# LED.net
KiCad netlist of a schematic drawn in Altium Designer
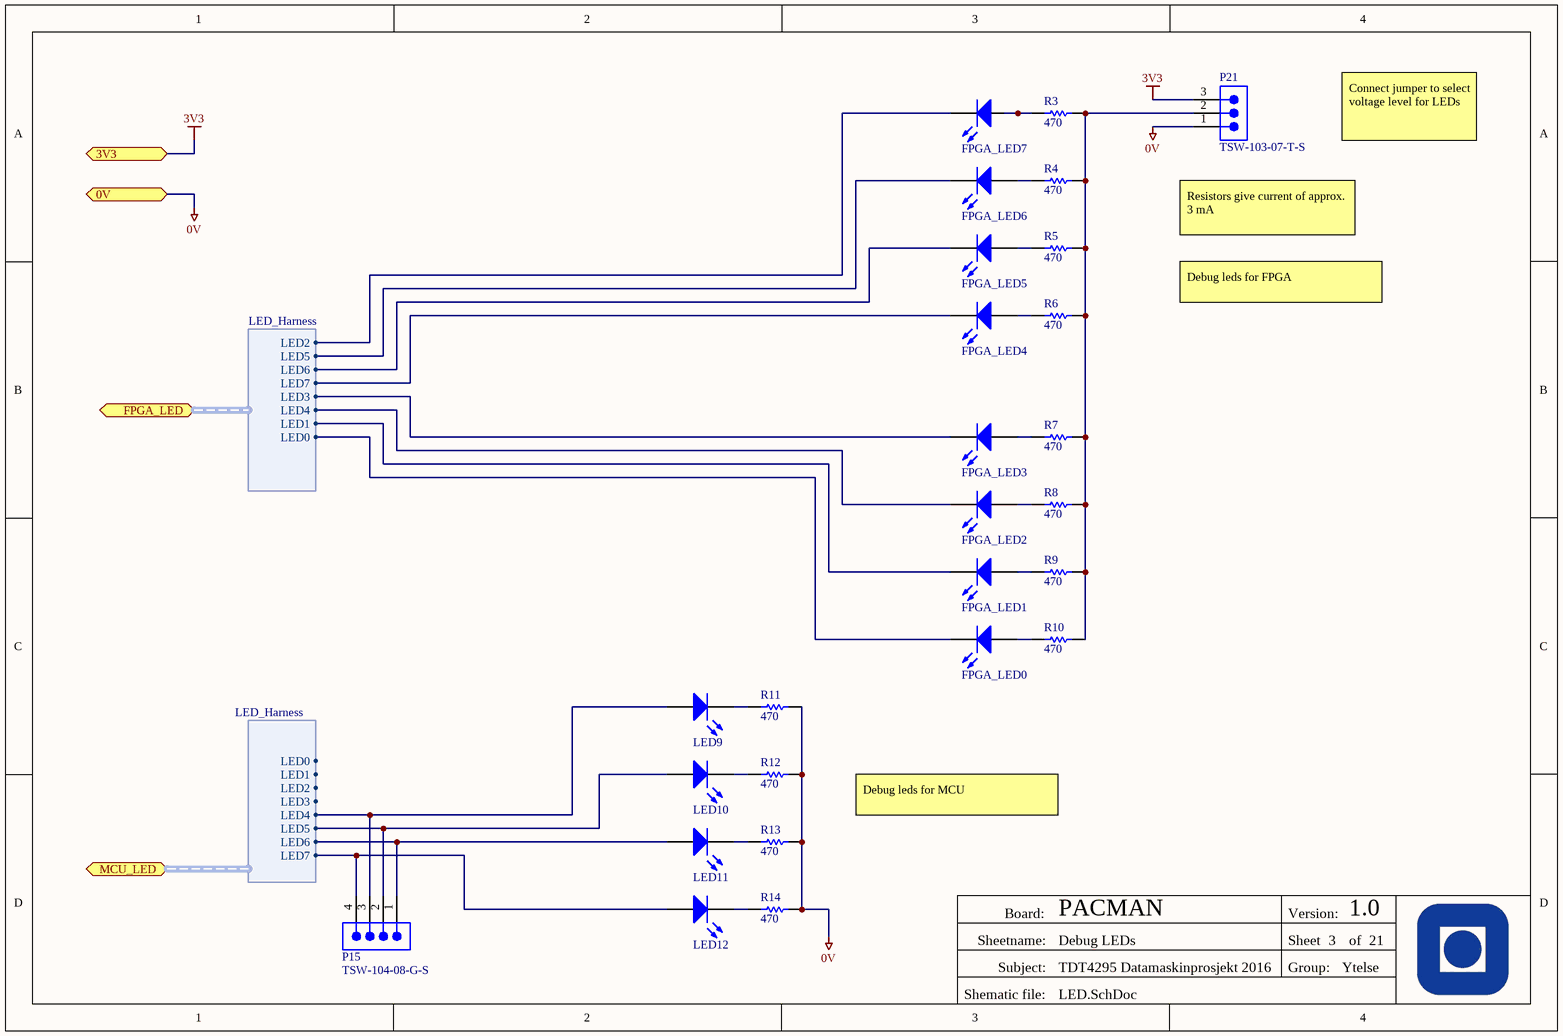
[diagram p0: LED.SchDoc]

(export (version "E")
  (design (tool "Eeschema 10.0.6"))
  (components
    (comp (ref "FPGA_LED0")
      (value "150060RS75000")
      (footprint "0603_A")
      (description "SMD mono-color Chip LED, WL-SMCW, Red")
      (fields (field (name "MANUFACTURER") "Wuerth Elektronik"))
      (libsource (lib "Altium Content Vault") (part "CMP-1426-00001-1"))
    )
    (comp (ref "FPGA_LED1")
      (value "150060RS75000")
      (footprint "0603_A")
      (description "SMD mono-color Chip LED, WL-SMCW, Red")
      (fields (field (name "MANUFACTURER") "Wuerth Elektronik"))
      (libsource (lib "Altium Content Vault") (part "CMP-1426-00001-1"))
    )
    (comp (ref "FPGA_LED2")
      (value "150060RS75000")
      (footprint "0603_A")
      (description "SMD mono-color Chip LED, WL-SMCW, Red")
      (fields (field (name "MANUFACTURER") "Wuerth Elektronik"))
      (libsource (lib "Altium Content Vault") (part "CMP-1426-00001-1"))
    )
    (comp (ref "FPGA_LED3")
      (value "150060RS75000")
      (footprint "0603_A")
      (description "SMD mono-color Chip LED, WL-SMCW, Red")
      (fields (field (name "MANUFACTURER") "Wuerth Elektronik"))
      (libsource (lib "Altium Content Vault") (part "CMP-1426-00001-1"))
    )
    (comp (ref "FPGA_LED4")
      (value "150060RS75000")
      (footprint "0603_A")
      (description "SMD mono-color Chip LED, WL-SMCW, Red")
      (fields (field (name "MANUFACTURER") "Wuerth Elektronik"))
      (libsource (lib "Altium Content Vault") (part "CMP-1426-00001-1"))
    )
    (comp (ref "FPGA_LED5")
      (value "150060RS75000")
      (footprint "0603_A")
      (description "SMD mono-color Chip LED, WL-SMCW, Red")
      (fields (field (name "MANUFACTURER") "Wuerth Elektronik"))
      (libsource (lib "Altium Content Vault") (part "CMP-1426-00001-1"))
    )
    (comp (ref "FPGA_LED6")
      (value "150060RS75000")
      (footprint "0603_A")
      (description "SMD mono-color Chip LED, WL-SMCW, Red")
      (fields (field (name "MANUFACTURER") "Wuerth Elektronik"))
      (libsource (lib "Altium Content Vault") (part "CMP-1426-00001-1"))
    )
    (comp (ref "FPGA_LED7")
      (value "150060RS75000")
      (footprint "0603_A")
      (description "SMD mono-color Chip LED, WL-SMCW, Red")
      (fields (field (name "MANUFACTURER") "Wuerth Elektronik"))
      (libsource (lib "Altium Content Vault") (part "CMP-1426-00001-1"))
    )
    (comp (ref "LED9")
      (value "150060RS75000")
      (footprint "0603_A")
      (description "SMD mono-color Chip LED, WL-SMCW, Red")
      (fields (field (name "MANUFACTURER") "Wuerth Elektronik"))
      (libsource (lib "Altium Content Vault") (part "CMP-1426-00001-1"))
    )
    (comp (ref "LED10")
      (value "150060RS75000")
      (footprint "0603_A")
      (description "SMD mono-color Chip LED, WL-SMCW, Red")
      (fields (field (name "MANUFACTURER") "Wuerth Elektronik"))
      (libsource (lib "Altium Content Vault") (part "CMP-1426-00001-1"))
    )
    (comp (ref "LED11")
      (value "150060RS75000")
      (footprint "0603_A")
      (description "SMD mono-color Chip LED, WL-SMCW, Red")
      (fields (field (name "MANUFACTURER") "Wuerth Elektronik"))
      (libsource (lib "Altium Content Vault") (part "CMP-1426-00001-1"))
    )
    (comp (ref "LED12")
      (value "150060RS75000")
      (footprint "0603_A")
      (description "SMD mono-color Chip LED, WL-SMCW, Red")
      (fields (field (name "MANUFACTURER") "Wuerth Elektronik"))
      (libsource (lib "Altium Content Vault") (part "CMP-1426-00001-1"))
    )
    (comp (ref "P15")
      (value "TSW-104-08-G-S")
      (footprint "SMTC-TSW-104-08-X-S")
      (description "0.025\" SQ Post Header, Through-hole, Vertical, -55 to 125 degC, 2.54 mm Pitch, 4-Pin, Male, RoHS")
      (fields (field (name "MANUFACTURER") "Samtec"))
      (libsource (lib "Altium Content Vault") (part "SMTC-TSW-104-08-X-S"))
    )
    (comp (ref "P21")
      (value "TSW-103-07-T-S")
      (footprint "SMTC-TSW-103-07-X-S")
      (fields (field (name "MANUFACTURER") "Samtec"))
      (libsource (lib "Altium Content Vault") (part "SMTC-TSW-103-X-X-S-X"))
    )
    (comp (ref "R3")
      (value "470")
      (footprint "RESC0603(1608)_N")
      (description "470R 0.1W 5% 0603 (1608 Metric)  SMD")
      (fields (field (name "TOLERANCE") "5 %") (field (name "POWER") "0.1 W"))
      (libsource (lib "Altium Content Vault") (part "CMP-1012-00066-1"))
    )
    (comp (ref "R4")
      (value "470")
      (footprint "RESC0603(1608)_N")
      (description "470R 0.1W 5% 0603 (1608 Metric)  SMD")
      (fields (field (name "TOLERANCE") "5 %") (field (name "POWER") "0.1 W"))
      (libsource (lib "Altium Content Vault") (part "CMP-1012-00066-1"))
    )
    (comp (ref "R5")
      (value "470")
      (footprint "RESC0603(1608)_N")
      (description "470R 0.1W 5% 0603 (1608 Metric)  SMD")
      (fields (field (name "TOLERANCE") "5 %") (field (name "POWER") "0.1 W"))
      (libsource (lib "Altium Content Vault") (part "CMP-1012-00066-1"))
    )
    (comp (ref "R6")
      (value "470")
      (footprint "RESC0603(1608)_N")
      (description "470R 0.1W 5% 0603 (1608 Metric)  SMD")
      (fields (field (name "TOLERANCE") "5 %") (field (name "POWER") "0.1 W"))
      (libsource (lib "Altium Content Vault") (part "CMP-1012-00066-1"))
    )
    (comp (ref "R7")
      (value "470")
      (footprint "RESC0603(1608)_N")
      (description "470R 0.1W 5% 0603 (1608 Metric)  SMD")
      (fields (field (name "TOLERANCE") "5 %") (field (name "POWER") "0.1 W"))
      (libsource (lib "Altium Content Vault") (part "CMP-1012-00066-1"))
    )
    (comp (ref "R8")
      (value "470")
      (footprint "RESC0603(1608)_N")
      (description "470R 0.1W 5% 0603 (1608 Metric)  SMD")
      (fields (field (name "TOLERANCE") "5 %") (field (name "POWER") "0.1 W"))
      (libsource (lib "Altium Content Vault") (part "CMP-1012-00066-1"))
    )
    (comp (ref "R9")
      (value "470")
      (footprint "RESC0603(1608)_N")
      (description "470R 0.1W 5% 0603 (1608 Metric)  SMD")
      (fields (field (name "TOLERANCE") "5 %") (field (name "POWER") "0.1 W"))
      (libsource (lib "Altium Content Vault") (part "CMP-1012-00066-1"))
    )
    (comp (ref "R10")
      (value "470")
      (footprint "RESC0603(1608)_N")
      (description "470R 0.1W 5% 0603 (1608 Metric)  SMD")
      (fields (field (name "TOLERANCE") "5 %") (field (name "POWER") "0.1 W"))
      (libsource (lib "Altium Content Vault") (part "CMP-1012-00066-1"))
    )
    (comp (ref "R11")
      (value "470")
      (footprint "RESC0603(1608)_N")
      (description "470R 0.1W 5% 0603 (1608 Metric)  SMD")
      (fields (field (name "TOLERANCE") "5 %") (field (name "POWER") "0.1 W"))
      (libsource (lib "Altium Content Vault") (part "CMP-1012-00066-1"))
    )
    (comp (ref "R12")
      (value "470")
      (footprint "RESC0603(1608)_N")
      (description "470R 0.1W 5% 0603 (1608 Metric)  SMD")
      (fields (field (name "TOLERANCE") "5 %") (field (name "POWER") "0.1 W"))
      (libsource (lib "Altium Content Vault") (part "CMP-1012-00066-1"))
    )
    (comp (ref "R13")
      (value "470")
      (footprint "RESC0603(1608)_N")
      (description "470R 0.1W 5% 0603 (1608 Metric)  SMD")
      (fields (field (name "TOLERANCE") "5 %") (field (name "POWER") "0.1 W"))
      (libsource (lib "Altium Content Vault") (part "CMP-1012-00066-1"))
    )
    (comp (ref "R14")
      (value "470")
      (footprint "RESC0603(1608)_N")
      (description "470R 0.1W 5% 0603 (1608 Metric)  SMD")
      (fields (field (name "TOLERANCE") "5 %") (field (name "POWER") "0.1 W"))
      (libsource (lib "Altium Content Vault") (part "CMP-1012-00066-1"))
    )
  )
  (nets
    (net (code "3") (name "0V") (class "Default")
      (node (ref "P21") (pin "1") (pinfunction "1_1") (pintype "passive"))
      (node (ref "R11") (pin "2") (pinfunction "2_2") (pintype "passive"))
      (node (ref "R12") (pin "2") (pinfunction "2_2") (pintype "passive"))
      (node (ref "R13") (pin "2") (pinfunction "2_2") (pintype "passive"))
      (node (ref "R14") (pin "2") (pinfunction "2_2") (pintype "passive"))
    )
    (net (code "4") (name "3V3") (class "Default")
      (node (ref "P21") (pin "3") (pinfunction "3_3") (pintype "passive"))
    )
    (net (code "5") (name "Net-(FPGA_LED0-A)") (class "Default")
      (node (ref "FPGA_LED0") (pin "2") (pinfunction "A_2") (pintype "passive"))
      (node (ref "R10") (pin "1") (pinfunction "1_1") (pintype "passive"))
    )
    (net (code "6") (name "Net-(FPGA_LED1-A)") (class "Default")
      (node (ref "FPGA_LED1") (pin "2") (pinfunction "A_2") (pintype "passive"))
      (node (ref "R9") (pin "1") (pinfunction "1_1") (pintype "passive"))
    )
    (net (code "7") (name "Net-(FPGA_LED2-A)") (class "Default")
      (node (ref "FPGA_LED2") (pin "2") (pinfunction "A_2") (pintype "passive"))
      (node (ref "R8") (pin "1") (pinfunction "1_1") (pintype "passive"))
    )
    (net (code "8") (name "Net-(FPGA_LED3-A)") (class "Default")
      (node (ref "FPGA_LED3") (pin "2") (pinfunction "A_2") (pintype "passive"))
      (node (ref "R7") (pin "1") (pinfunction "1_1") (pintype "passive"))
    )
    (net (code "9") (name "Net-(FPGA_LED4-A)") (class "Default")
      (node (ref "FPGA_LED4") (pin "2") (pinfunction "A_2") (pintype "passive"))
      (node (ref "R6") (pin "1") (pinfunction "1_1") (pintype "passive"))
    )
    (net (code "10") (name "Net-(FPGA_LED5-A)") (class "Default")
      (node (ref "FPGA_LED5") (pin "2") (pinfunction "A_2") (pintype "passive"))
      (node (ref "R5") (pin "1") (pinfunction "1_1") (pintype "passive"))
    )
    (net (code "11") (name "Net-(FPGA_LED6-A)") (class "Default")
      (node (ref "FPGA_LED6") (pin "2") (pinfunction "A_2") (pintype "passive"))
      (node (ref "R4") (pin "1") (pinfunction "1_1") (pintype "passive"))
    )
    (net (code "12") (name "Net-(FPGA_LED7-A)") (class "Default")
      (node (ref "FPGA_LED7") (pin "2") (pinfunction "A_2") (pintype "passive"))
      (node (ref "R3") (pin "1") (pinfunction "1_1") (pintype "passive"))
    )
    (net (code "13") (name "Net-(LED9-A)") (class "Default")
      (node (ref "LED9") (pin "2") (pinfunction "A_2") (pintype "passive"))
      (node (ref "P15") (pin "3") (pinfunction "3_3") (pintype "passive"))
    )
    (net (code "14") (name "Net-(LED9-K)") (class "Default")
      (node (ref "LED9") (pin "1") (pinfunction "K_1") (pintype "passive"))
      (node (ref "R11") (pin "1") (pinfunction "1_1") (pintype "passive"))
    )
    (net (code "15") (name "Net-(LED10-A)") (class "Default")
      (node (ref "LED10") (pin "2") (pinfunction "A_2") (pintype "passive"))
      (node (ref "P15") (pin "2") (pinfunction "2_2") (pintype "passive"))
    )
    (net (code "16") (name "Net-(LED10-K)") (class "Default")
      (node (ref "LED10") (pin "1") (pinfunction "K_1") (pintype "passive"))
      (node (ref "R12") (pin "1") (pinfunction "1_1") (pintype "passive"))
    )
    (net (code "17") (name "Net-(LED11-A)") (class "Default")
      (node (ref "LED11") (pin "2") (pinfunction "A_2") (pintype "passive"))
      (node (ref "P15") (pin "1") (pinfunction "1_1") (pintype "passive"))
    )
    (net (code "18") (name "Net-(LED11-K)") (class "Default")
      (node (ref "LED11") (pin "1") (pinfunction "K_1") (pintype "passive"))
      (node (ref "R13") (pin "1") (pinfunction "1_1") (pintype "passive"))
    )
    (net (code "19") (name "Net-(LED12-A)") (class "Default")
      (node (ref "LED12") (pin "2") (pinfunction "A_2") (pintype "passive"))
      (node (ref "P15") (pin "4") (pinfunction "4_4") (pintype "passive"))
    )
    (net (code "20") (name "Net-(LED12-K)") (class "Default")
      (node (ref "LED12") (pin "1") (pinfunction "K_1") (pintype "passive"))
      (node (ref "R14") (pin "1") (pinfunction "1_1") (pintype "passive"))
    )
    (net (code "21") (name "Net-(P21-Pad2)") (class "Default")
      (node (ref "P21") (pin "2") (pinfunction "2_2") (pintype "passive"))
      (node (ref "R10") (pin "2") (pinfunction "2_2") (pintype "passive"))
      (node (ref "R3") (pin "2") (pinfunction "2_2") (pintype "passive"))
      (node (ref "R4") (pin "2") (pinfunction "2_2") (pintype "passive"))
      (node (ref "R5") (pin "2") (pinfunction "2_2") (pintype "passive"))
      (node (ref "R6") (pin "2") (pinfunction "2_2") (pintype "passive"))
      (node (ref "R7") (pin "2") (pinfunction "2_2") (pintype "passive"))
      (node (ref "R8") (pin "2") (pinfunction "2_2") (pintype "passive"))
      (node (ref "R9") (pin "2") (pinfunction "2_2") (pintype "passive"))
    )
    (net (code "22") (name "unconnected-(FPGA_LED0-K-Pad1)") (class "Default")
      (node (ref "FPGA_LED0") (pin "1") (pinfunction "K_1") (pintype "passive"))
    )
    (net (code "23") (name "unconnected-(FPGA_LED1-K-Pad1)") (class "Default")
      (node (ref "FPGA_LED1") (pin "1") (pinfunction "K_1") (pintype "passive"))
    )
    (net (code "24") (name "unconnected-(FPGA_LED2-K-Pad1)") (class "Default")
      (node (ref "FPGA_LED2") (pin "1") (pinfunction "K_1") (pintype "passive"))
    )
    (net (code "25") (name "unconnected-(FPGA_LED3-K-Pad1)") (class "Default")
      (node (ref "FPGA_LED3") (pin "1") (pinfunction "K_1") (pintype "passive"))
    )
    (net (code "26") (name "unconnected-(FPGA_LED4-K-Pad1)") (class "Default")
      (node (ref "FPGA_LED4") (pin "1") (pinfunction "K_1") (pintype "passive"))
    )
    (net (code "27") (name "unconnected-(FPGA_LED5-K-Pad1)") (class "Default")
      (node (ref "FPGA_LED5") (pin "1") (pinfunction "K_1") (pintype "passive"))
    )
    (net (code "28") (name "unconnected-(FPGA_LED6-K-Pad1)") (class "Default")
      (node (ref "FPGA_LED6") (pin "1") (pinfunction "K_1") (pintype "passive"))
    )
    (net (code "29") (name "unconnected-(FPGA_LED7-K-Pad1)") (class "Default")
      (node (ref "FPGA_LED7") (pin "1") (pinfunction "K_1") (pintype "passive"))
    )
  )
)
